# ESPMODULE-E_B_EL-VENOM.net
KiCad netlist of a schematic drawn in Altium Designer
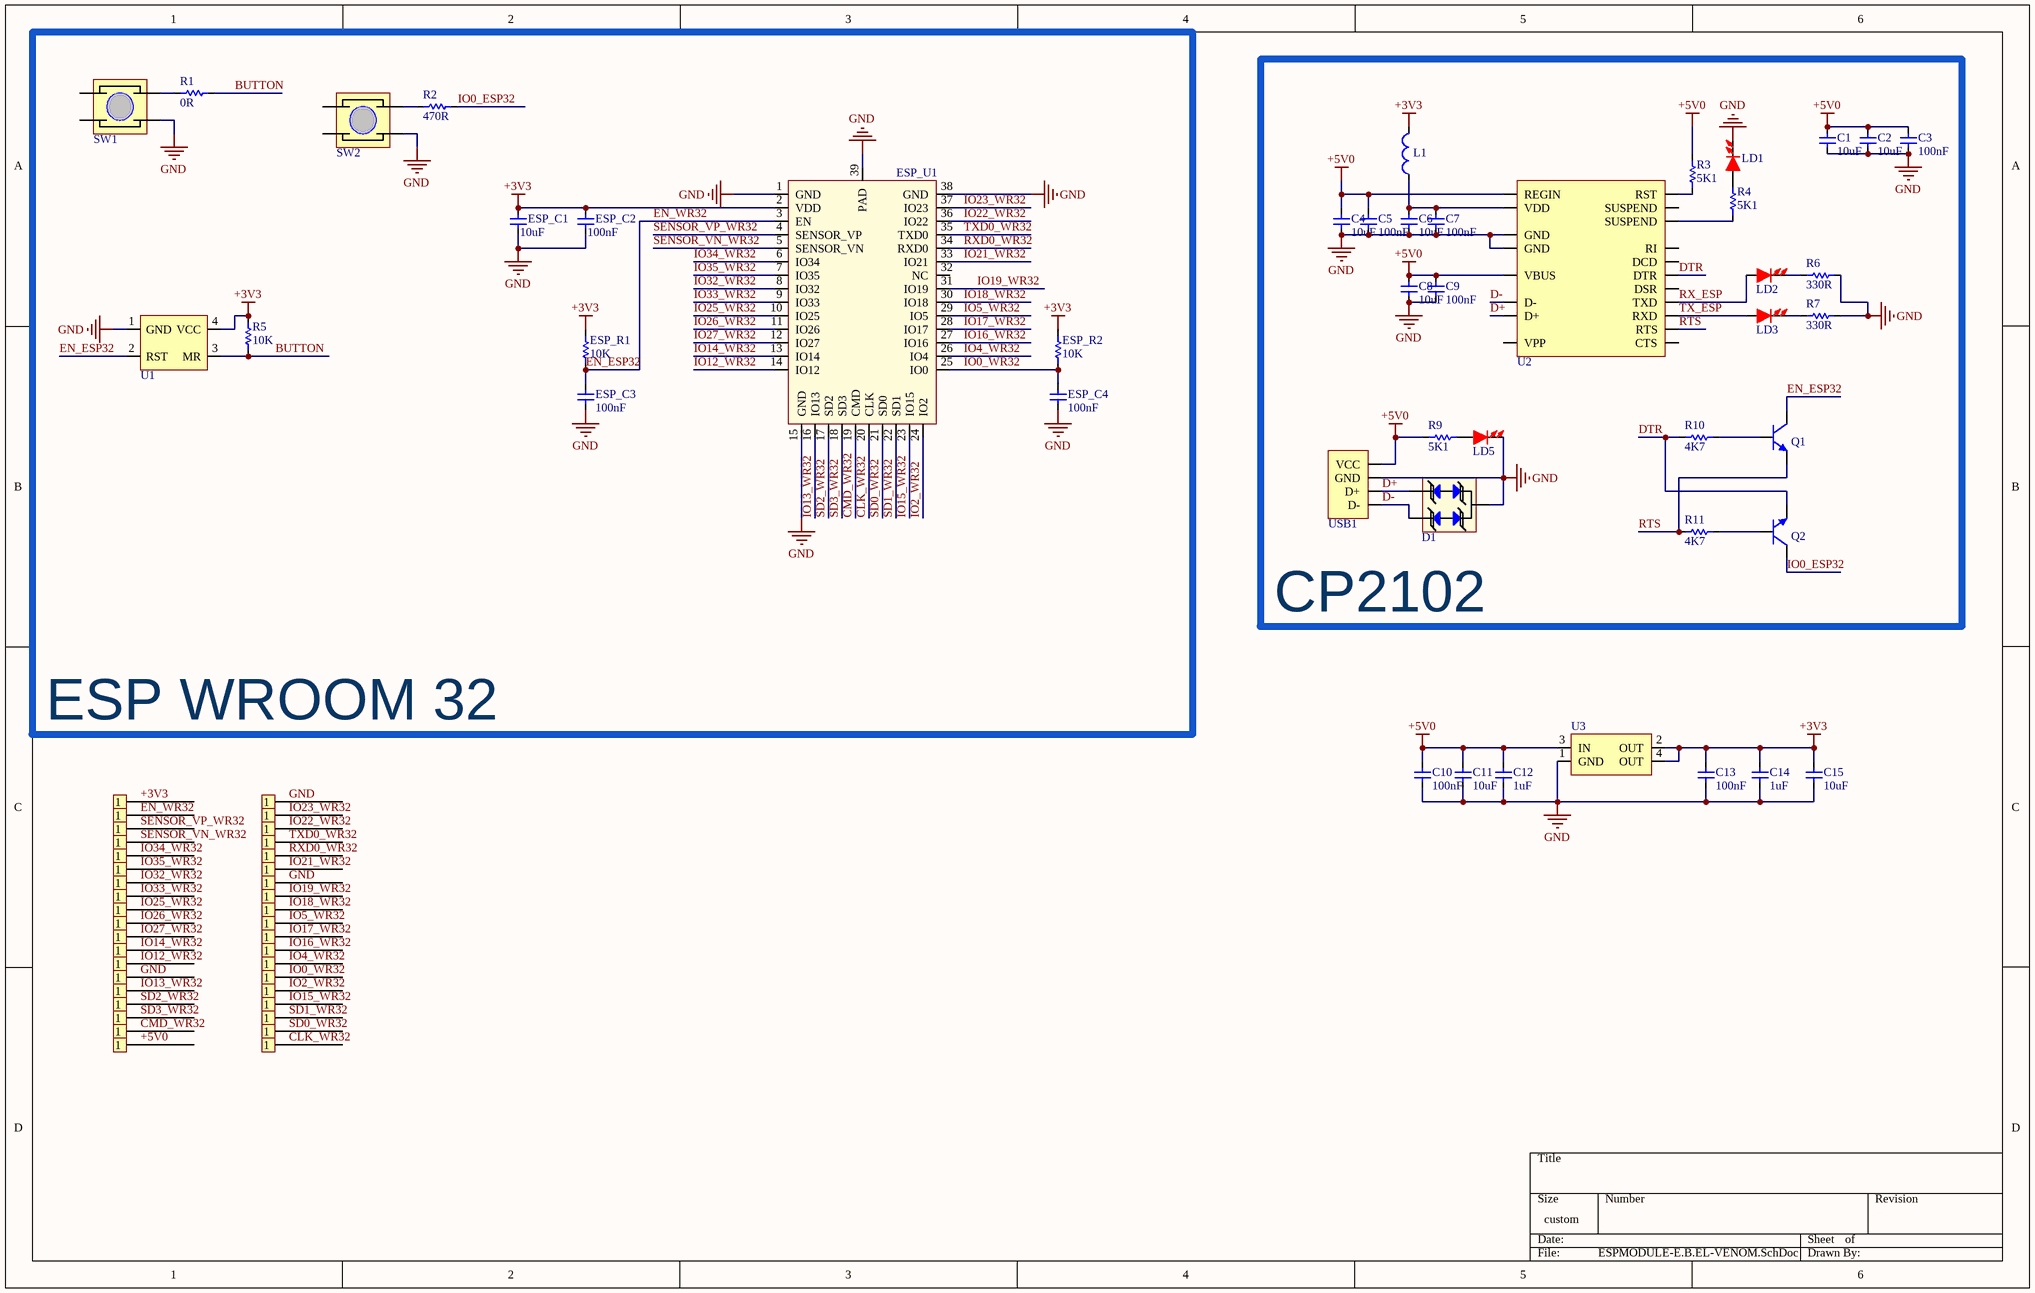
[diagram p0: ESPMODULE-E.B.EL-VENOM.SchDoc]

(export (version "E")
  (design (tool "Eeschema 10.0.6"))
  (components
    (comp (ref "C1")
      (value "10uF")
      (footprint "0805C")
      (description "CAP 0805 10uF 16V X5R")
      (libsource (lib "Ake Library") (part "Capacitor"))
    )
    (comp (ref "C2")
      (value "10uF")
      (footprint "0805C")
      (description "CAP 0805 10uF 16V X5R")
      (libsource (lib "Ake Library") (part "Capacitor"))
    )
    (comp (ref "C3")
      (value "100nF")
      (footprint "0603C")
      (description "CAP 0603 100nF 50V X7R")
      (libsource (lib "Ake Library") (part "Capacitor"))
    )
    (comp (ref "C4")
      (value "10uF")
      (footprint "0805C")
      (description "CAP 0805 10uF 16V X5R")
      (libsource (lib "Ake Library") (part "Capacitor"))
    )
    (comp (ref "C5")
      (value "100nF")
      (footprint "0603C")
      (description "CAP 0603 100nF 50V X7R")
      (libsource (lib "Ake Library") (part "Capacitor"))
    )
    (comp (ref "C6")
      (value "10uF")
      (footprint "0805C")
      (description "CAP 0805 10uF 16V X5R")
      (libsource (lib "Ake Library") (part "Capacitor"))
    )
    (comp (ref "C7")
      (value "100nF")
      (footprint "0603C")
      (description "CAP 0603 100nF 50V X7R")
      (libsource (lib "Ake Library") (part "Capacitor"))
    )
    (comp (ref "C8")
      (value "10uF")
      (footprint "0805C")
      (description "CAP 0805 10uF 16V X5R")
      (libsource (lib "Ake Library") (part "Capacitor"))
    )
    (comp (ref "C9")
      (value "100nF")
      (footprint "0603C")
      (description "CAP 0603 100nF 50V X7R")
      (libsource (lib "Ake Library") (part "Capacitor"))
    )
    (comp (ref "C10")
      (value "100nF")
      (footprint "0603C")
      (description "CAP 0603 100nF 50V X7R")
      (libsource (lib "Ake Library") (part "Capacitor"))
    )
    (comp (ref "C11")
      (value "10uF")
      (footprint "0805C")
      (description "CAP 0805 10uF 16V X5R")
      (libsource (lib "Ake Library") (part "Capacitor"))
    )
    (comp (ref "C12")
      (value "1uF")
      (footprint "0603C")
      (description "CAP 0603 1uF 16V X5R")
      (libsource (lib "Ake Library") (part "Capacitor"))
    )
    (comp (ref "C13")
      (value "100nF")
      (footprint "0603C")
      (description "CAP 0603 100nF 50V X7R")
      (libsource (lib "Ake Library") (part "Capacitor"))
    )
    (comp (ref "C14")
      (value "1uF")
      (footprint "0603C")
      (description "CAP 0603 1uF 16V X5R")
      (libsource (lib "Ake Library") (part "Capacitor"))
    )
    (comp (ref "C15")
      (value "10uF")
      (footprint "0805C")
      (description "CAP 0805 10uF 16V X5R")
      (libsource (lib "Ake Library") (part "Capacitor"))
    )
    (comp (ref "CON1")
      (value "Connector 1p")
      (footprint "HEADER 1 DIP ERKEK 180")
      (description "P.HEADER 1x40 PIN 180 DERECE DIP ERKEK")
      (libsource (lib "Ake Library") (part "Connector 1p"))
    )
    (comp (ref "CON2")
      (value "Connector 1p")
      (footprint "HEADER 1 DIP ERKEK 180")
      (description "P.HEADER 1x40 PIN 180 DERECE DIP ERKEK")
      (libsource (lib "Ake Library") (part "Connector 1p"))
    )
    (comp (ref "CON3")
      (value "Connector 1p")
      (footprint "HEADER 1 DIP ERKEK 180")
      (description "P.HEADER 1x40 PIN 180 DERECE DIP ERKEK")
      (libsource (lib "Ake Library") (part "Connector 1p"))
    )
    (comp (ref "CON4")
      (value "Connector 1p")
      (footprint "HEADER 1 DIP ERKEK 180")
      (description "P.HEADER 1x40 PIN 180 DERECE DIP ERKEK")
      (libsource (lib "Ake Library") (part "Connector 1p"))
    )
    (comp (ref "CON5")
      (value "Connector 1p")
      (footprint "HEADER 1 DIP ERKEK 180")
      (description "P.HEADER 1x40 PIN 180 DERECE DIP ERKEK")
      (libsource (lib "Ake Library") (part "Connector 1p"))
    )
    (comp (ref "CON6")
      (value "Connector 1p")
      (footprint "HEADER 1 DIP ERKEK 180")
      (description "P.HEADER 1x40 PIN 180 DERECE DIP ERKEK")
      (libsource (lib "Ake Library") (part "Connector 1p"))
    )
    (comp (ref "CON7")
      (value "Connector 1p")
      (footprint "HEADER 1 DIP ERKEK 180")
      (description "P.HEADER 1x40 PIN 180 DERECE DIP ERKEK")
      (libsource (lib "Ake Library") (part "Connector 1p"))
    )
    (comp (ref "CON8")
      (value "Connector 1p")
      (footprint "HEADER 1 DIP ERKEK 180")
      (description "P.HEADER 1x40 PIN 180 DERECE DIP ERKEK")
      (libsource (lib "Ake Library") (part "Connector 1p"))
    )
    (comp (ref "CON9")
      (value "Connector 1p")
      (footprint "HEADER 1 DIP ERKEK 180")
      (description "P.HEADER 1x40 PIN 180 DERECE DIP ERKEK")
      (libsource (lib "Ake Library") (part "Connector 1p"))
    )
    (comp (ref "CON10")
      (value "Connector 1p")
      (footprint "HEADER 1 DIP ERKEK 180")
      (description "P.HEADER 1x40 PIN 180 DERECE DIP ERKEK")
      (libsource (lib "Ake Library") (part "Connector 1p"))
    )
    (comp (ref "CON11")
      (value "Connector 1p")
      (footprint "HEADER 1 DIP ERKEK 180")
      (description "P.HEADER 1x40 PIN 180 DERECE DIP ERKEK")
      (libsource (lib "Ake Library") (part "Connector 1p"))
    )
    (comp (ref "CON12")
      (value "Connector 1p")
      (footprint "HEADER 1 DIP ERKEK 180")
      (description "P.HEADER 1x40 PIN 180 DERECE DIP ERKEK")
      (libsource (lib "Ake Library") (part "Connector 1p"))
    )
    (comp (ref "CON13")
      (value "Connector 1p")
      (footprint "HEADER 1 DIP ERKEK 180")
      (description "P.HEADER 1x40 PIN 180 DERECE DIP ERKEK")
      (libsource (lib "Ake Library") (part "Connector 1p"))
    )
    (comp (ref "CON14")
      (value "Connector 1p")
      (footprint "HEADER 1 DIP ERKEK 180")
      (description "P.HEADER 1x40 PIN 180 DERECE DIP ERKEK")
      (libsource (lib "Ake Library") (part "Connector 1p"))
    )
    (comp (ref "CON15")
      (value "Connector 1p")
      (footprint "HEADER 1 DIP ERKEK 180")
      (description "P.HEADER 1x40 PIN 180 DERECE DIP ERKEK")
      (libsource (lib "Ake Library") (part "Connector 1p"))
    )
    (comp (ref "CON16")
      (value "Connector 1p")
      (footprint "HEADER 1 DIP ERKEK 180")
      (description "P.HEADER 1x40 PIN 180 DERECE DIP ERKEK")
      (libsource (lib "Ake Library") (part "Connector 1p"))
    )
    (comp (ref "CON17")
      (value "Connector 1p")
      (footprint "HEADER 1 DIP ERKEK 180")
      (description "P.HEADER 1x40 PIN 180 DERECE DIP ERKEK")
      (libsource (lib "Ake Library") (part "Connector 1p"))
    )
    (comp (ref "CON18")
      (value "Connector 1p")
      (footprint "HEADER 1 DIP ERKEK 180")
      (description "P.HEADER 1x40 PIN 180 DERECE DIP ERKEK")
      (libsource (lib "Ake Library") (part "Connector 1p"))
    )
    (comp (ref "CON19")
      (value "Connector 1p")
      (footprint "HEADER 1 DIP ERKEK 180")
      (description "P.HEADER 1x40 PIN 180 DERECE DIP ERKEK")
      (libsource (lib "Ake Library") (part "Connector 1p"))
    )
    (comp (ref "CON20")
      (value "Connector 1p")
      (footprint "HEADER 1 DIP ERKEK 180")
      (description "P.HEADER 1x40 PIN 180 DERECE DIP ERKEK")
      (libsource (lib "Ake Library") (part "Connector 1p"))
    )
    (comp (ref "CON21")
      (value "Connector 1p")
      (footprint "HEADER 1 DIP ERKEK 180")
      (description "P.HEADER 1x40 PIN 180 DERECE DIP ERKEK")
      (libsource (lib "Ake Library") (part "Connector 1p"))
    )
    (comp (ref "CON22")
      (value "Connector 1p")
      (footprint "HEADER 1 DIP ERKEK 180")
      (description "P.HEADER 1x40 PIN 180 DERECE DIP ERKEK")
      (libsource (lib "Ake Library") (part "Connector 1p"))
    )
    (comp (ref "CON23")
      (value "Connector 1p")
      (footprint "HEADER 1 DIP ERKEK 180")
      (description "P.HEADER 1x40 PIN 180 DERECE DIP ERKEK")
      (libsource (lib "Ake Library") (part "Connector 1p"))
    )
    (comp (ref "CON24")
      (value "Connector 1p")
      (footprint "HEADER 1 DIP ERKEK 180")
      (description "P.HEADER 1x40 PIN 180 DERECE DIP ERKEK")
      (libsource (lib "Ake Library") (part "Connector 1p"))
    )
    (comp (ref "CON25")
      (value "Connector 1p")
      (footprint "HEADER 1 DIP ERKEK 180")
      (description "P.HEADER 1x40 PIN 180 DERECE DIP ERKEK")
      (libsource (lib "Ake Library") (part "Connector 1p"))
    )
    (comp (ref "CON26")
      (value "Connector 1p")
      (footprint "HEADER 1 DIP ERKEK 180")
      (description "P.HEADER 1x40 PIN 180 DERECE DIP ERKEK")
      (libsource (lib "Ake Library") (part "Connector 1p"))
    )
    (comp (ref "CON27")
      (value "Connector 1p")
      (footprint "HEADER 1 DIP ERKEK 180")
      (description "P.HEADER 1x40 PIN 180 DERECE DIP ERKEK")
      (libsource (lib "Ake Library") (part "Connector 1p"))
    )
    (comp (ref "CON28")
      (value "Connector 1p")
      (footprint "HEADER 1 DIP ERKEK 180")
      (description "P.HEADER 1x40 PIN 180 DERECE DIP ERKEK")
      (libsource (lib "Ake Library") (part "Connector 1p"))
    )
    (comp (ref "CON29")
      (value "Connector 1p")
      (footprint "HEADER 1 DIP ERKEK 180")
      (description "P.HEADER 1x40 PIN 180 DERECE DIP ERKEK")
      (libsource (lib "Ake Library") (part "Connector 1p"))
    )
    (comp (ref "CON30")
      (value "Connector 1p")
      (footprint "HEADER 1 DIP ERKEK 180")
      (description "P.HEADER 1x40 PIN 180 DERECE DIP ERKEK")
      (libsource (lib "Ake Library") (part "Connector 1p"))
    )
    (comp (ref "CON31")
      (value "Connector 1p")
      (footprint "HEADER 1 DIP ERKEK 180")
      (description "P.HEADER 1x40 PIN 180 DERECE DIP ERKEK")
      (libsource (lib "Ake Library") (part "Connector 1p"))
    )
    (comp (ref "CON32")
      (value "Connector 1p")
      (footprint "HEADER 1 DIP ERKEK 180")
      (description "P.HEADER 1x40 PIN 180 DERECE DIP ERKEK")
      (libsource (lib "Ake Library") (part "Connector 1p"))
    )
    (comp (ref "CON33")
      (value "Connector 1p")
      (footprint "HEADER 1 DIP ERKEK 180")
      (description "P.HEADER 1x40 PIN 180 DERECE DIP ERKEK")
      (libsource (lib "Ake Library") (part "Connector 1p"))
    )
    (comp (ref "CON34")
      (value "Connector 1p")
      (footprint "HEADER 1 DIP ERKEK 180")
      (description "P.HEADER 1x40 PIN 180 DERECE DIP ERKEK")
      (libsource (lib "Ake Library") (part "Connector 1p"))
    )
    (comp (ref "CON35")
      (value "Connector 1p")
      (footprint "HEADER 1 DIP ERKEK 180")
      (description "P.HEADER 1x40 PIN 180 DERECE DIP ERKEK")
      (libsource (lib "Ake Library") (part "Connector 1p"))
    )
    (comp (ref "CON36")
      (value "Connector 1p")
      (footprint "HEADER 1 DIP ERKEK 180")
      (description "P.HEADER 1x40 PIN 180 DERECE DIP ERKEK")
      (libsource (lib "Ake Library") (part "Connector 1p"))
    )
    (comp (ref "CON37")
      (value "Connector 1p")
      (footprint "HEADER 1 DIP ERKEK 180")
      (description "P.HEADER 1x40 PIN 180 DERECE DIP ERKEK")
      (libsource (lib "Ake Library") (part "Connector 1p"))
    )
    (comp (ref "CON38")
      (value "Connector 1p")
      (footprint "HEADER 1 DIP ERKEK 180")
      (description "P.HEADER 1x40 PIN 180 DERECE DIP ERKEK")
      (libsource (lib "Ake Library") (part "Connector 1p"))
    )
    (comp (ref "D1")
      (value "TVS Diode 3p")
      (footprint "SOT23")
      (description "CDSOT23-SM712 DIODE TVS 400W 26V")
      (libsource (lib "Ake Library") (part "TVS Diode 3p"))
    )
    (comp (ref "ESP_C1")
      (value "10uF")
      (footprint "0805C")
      (description "CAP 0805 10uF 16V X5R")
      (libsource (lib "Ake Library") (part "Capacitor"))
    )
    (comp (ref "ESP_C2")
      (value "100nF")
      (footprint "0603C")
      (description "CAP 0603 100nF 50V X7R")
      (libsource (lib "Ake Library") (part "Capacitor"))
    )
    (comp (ref "ESP_C3")
      (value "100nF")
      (footprint "0603C")
      (description "CAP 0603 100nF 50V X7R")
      (libsource (lib "Ake Library") (part "Capacitor"))
    )
    (comp (ref "ESP_C4")
      (value "100nF")
      (footprint "0603C")
      (description "CAP 0603 100nF 50V X7R")
      (libsource (lib "Ake Library") (part "Capacitor"))
    )
    (comp (ref "ESP_R1")
      (value "10K")
      (footprint "0603R")
      (description "RES 0603 10K 1% 1/10W-S")
      (libsource (lib "Ake Library") (part "Resistor"))
    )
    (comp (ref "ESP_R2")
      (value "10K")
      (footprint "0603R")
      (description "RES 0603 10K 1% 1/10W-S")
      (libsource (lib "Ake Library") (part "Resistor"))
    )
    (comp (ref "ESP_U1")
      (value "ESP_WROOM_32")
      (footprint "ESP-WROOM-32")
      (description "ESP-WROOM-32 WİFİ MODULÜ")
      (libsource (lib "Ake Library") (part "ESP-WROOM-32"))
    )
    (comp (ref "L1")
      (value "Ferrite")
      (footprint "0805L")
      (description "INDUCTOR 2K5 SMD 0805 FERRITE 250mA")
      (libsource (lib "Ake Library") (part "Ferrite"))
    )
    (comp (ref "LD1")
      (value "LED")
      (footprint "0805LED")
      (description "LED GREEN SMD 0805")
      (libsource (lib "Ake Library") (part "LED"))
    )
    (comp (ref "LD2")
      (value "LED")
      (footprint "0805LED")
      (description "LED GREEN SMD 0805")
      (libsource (lib "Ake Library") (part "LED"))
    )
    (comp (ref "LD3")
      (value "LED")
      (footprint "0805LED")
      (description "LED BLUE SMD 0805")
      (libsource (lib "Ake Library") (part "LED"))
    )
    (comp (ref "LD5")
      (value "LED")
      (footprint "0805LED")
      (description "LED RED SMD 0805")
      (libsource (lib "Ake Library") (part "LED"))
    )
    (comp (ref "Q1")
      (value "NPN")
      (footprint "SOT23")
      (description "TRANSISTOR NPN BC817 0.5A SOT23")
      (libsource (lib "Ake Library") (part "NPN"))
    )
    (comp (ref "Q2")
      (value "NPN")
      (footprint "SOT23")
      (description "TRANSISTOR NPN BC817 0.5A SOT23")
      (libsource (lib "Ake Library") (part "NPN"))
    )
    (comp (ref "R1")
      (value "0R")
      (footprint "0603R")
      (description "RES 0603 0R 5% 1/10W-S")
      (libsource (lib "Ake Library") (part "Resistor"))
    )
    (comp (ref "R2")
      (value "470R")
      (footprint "0603R")
      (description "RES 0603 470R 1% 1/10W-S")
      (libsource (lib "Ake Library") (part "Resistor"))
    )
    (comp (ref "R3")
      (value "5K1")
      (footprint "0603R")
      (description "RES 0603 5K1 5% 1/10W-S")
      (libsource (lib "Ake Library") (part "Resistor"))
    )
    (comp (ref "R4")
      (value "5K1")
      (footprint "0603R")
      (description "RES 0603 5K1 5% 1/10W-S")
      (libsource (lib "Ake Library") (part "Resistor"))
    )
    (comp (ref "R5")
      (value "10K")
      (footprint "0603R")
      (description "RES 0603 10K 1% 1/10W-S")
      (libsource (lib "Ake Library") (part "Resistor"))
    )
    (comp (ref "R6")
      (value "330R")
      (footprint "0603R")
      (description "RES 0603 330R 5% 1/10W-S")
      (libsource (lib "Ake Library") (part "Resistor"))
    )
    (comp (ref "R7")
      (value "330R")
      (footprint "0603R")
      (description "RES 0603 330R 5% 1/10W-S")
      (libsource (lib "Ake Library") (part "Resistor"))
    )
    (comp (ref "R9")
      (value "5K1")
      (footprint "0603R")
      (description "RES 0603 5K1 5% 1/10W-S")
      (libsource (lib "Ake Library") (part "Resistor"))
    )
    (comp (ref "R10")
      (value "4K7")
      (footprint "0603R")
      (description "RES 0603 4K7 5% 1/10W-S")
      (libsource (lib "Ake Library") (part "Resistor"))
    )
    (comp (ref "R11")
      (value "4K7")
      (footprint "0603R")
      (description "RES 0603 4K7 5% 1/10W-S")
      (libsource (lib "Ake Library") (part "Resistor"))
    )
    (comp (ref "SW1")
      (value "Button")
      (footprint "BUTTON 6x6 4.3MM")
      (description "BUTTON 6x6 4.3MM")
      (libsource (lib "Ake Library") (part "Button"))
    )
    (comp (ref "SW2")
      (value "Button")
      (footprint "BUTTON 6x6 4.3MM")
      (description "BUTTON 6x6 4.3MM")
      (libsource (lib "Ake Library") (part "Button"))
    )
    (comp (ref "U1") (value "CAT811") (footprint "SOT-143") (libsource (lib "AkeLib") (part "CAT811")))
    (comp (ref "U2")
      (value "CP2102")
      (footprint "QFN-28 5x5x0.5")
      (description "CP2102-GMR USB TO UART BRIDGE 28VQFN")
      (libsource (lib "Ake Library") (part "CP2102"))
    )
    (comp (ref "U3")
      (value "LM1117")
      (footprint "SOT223")
      (description "REG 1117 3V3 SOT223")
      (libsource (lib "Ake Library") (part "LM1117"))
    )
    (comp (ref "USB1")
      (value "USB")
      (footprint "USB B MICRO 90")
      (description "MICRO USB CONNECTOR TYPE B 90")
      (libsource (lib "Ake Library") (part "USB"))
    )
  )
  (nets
    (net (code "1") (name "+3V3") (class "Default")
      (node (ref "C13") (pin "2") (pinfunction "2_2") (pintype "passive"))
      (node (ref "C14") (pin "2") (pinfunction "2_2") (pintype "passive"))
      (node (ref "C15") (pin "2") (pinfunction "2_2") (pintype "passive"))
      (node (ref "CON1") (pin "1") (pinfunction "1_1") (pintype "passive"))
      (node (ref "ESP_C1") (pin "2") (pinfunction "2_2") (pintype "passive"))
      (node (ref "ESP_C2") (pin "2") (pinfunction "2_2") (pintype "passive"))
      (node (ref "ESP_R1") (pin "2") (pinfunction "2_2") (pintype "passive"))
      (node (ref "ESP_R2") (pin "2") (pinfunction "2_2") (pintype "passive"))
      (node (ref "ESP_U1") (pin "2") (pinfunction "VDD_2") (pintype "passive"))
      (node (ref "L1") (pin "2") (pinfunction "2_2") (pintype "passive"))
      (node (ref "R5") (pin "2") (pinfunction "2_2") (pintype "passive"))
      (node (ref "U1") (pin "4") (pinfunction "VCC_4") (pintype "passive"))
      (node (ref "U3") (pin "2") (pinfunction "OUT_2") (pintype "power_in"))
      (node (ref "U3") (pin "4") (pinfunction "OUT_4") (pintype "power_in"))
    )
    (net (code "2") (name "+5V0") (class "Default")
      (node (ref "C1") (pin "2") (pinfunction "2_2") (pintype "passive"))
      (node (ref "C10") (pin "2") (pinfunction "2_2") (pintype "passive"))
      (node (ref "C11") (pin "2") (pinfunction "2_2") (pintype "passive"))
      (node (ref "C12") (pin "2") (pinfunction "2_2") (pintype "passive"))
      (node (ref "C2") (pin "2") (pinfunction "2_2") (pintype "passive"))
      (node (ref "C3") (pin "2") (pinfunction "2_2") (pintype "passive"))
      (node (ref "C4") (pin "2") (pinfunction "2_2") (pintype "passive"))
      (node (ref "C5") (pin "2") (pinfunction "2_2") (pintype "passive"))
      (node (ref "C8") (pin "2") (pinfunction "2_2") (pintype "passive"))
      (node (ref "C9") (pin "2") (pinfunction "2_2") (pintype "passive"))
      (node (ref "CON37") (pin "1") (pinfunction "1_1") (pintype "passive"))
      (node (ref "R3") (pin "2") (pinfunction "2_2") (pintype "passive"))
      (node (ref "R9") (pin "1") (pinfunction "1_1") (pintype "passive"))
      (node (ref "U2") (pin "7") (pinfunction "REGIN_7") (pintype "passive"))
      (node (ref "U2") (pin "8") (pinfunction "VBUS_8") (pintype "passive"))
      (node (ref "U3") (pin "3") (pinfunction "IN_3") (pintype "power_in"))
      (node (ref "USB1") (pin "VCC") (pinfunction "VCC_VCC") (pintype "passive"))
    )
    (net (code "3") (name "/BUTTON") (class "Default")
      (node (ref "R1") (pin "2") (pinfunction "2_2") (pintype "passive"))
      (node (ref "R5") (pin "1") (pinfunction "1_1") (pintype "passive"))
      (node (ref "U1") (pin "3") (pinfunction "MR_3") (pintype "passive"))
    )
    (net (code "4") (name "/CLK_WR32") (class "Default")
      (node (ref "CON38") (pin "1") (pinfunction "1_1") (pintype "passive"))
      (node (ref "ESP_U1") (pin "20") (pinfunction "CLK_20") (pintype "passive"))
    )
    (net (code "5") (name "/CMD_WR32") (class "Default")
      (node (ref "CON35") (pin "1") (pinfunction "1_1") (pintype "passive"))
      (node (ref "ESP_U1") (pin "19") (pinfunction "CMD_19") (pintype "passive"))
    )
    (net (code "6") (name "/D+") (class "Default")
      (node (ref "D1") (pin "2") (pinfunction "2_2") (pintype "passive"))
      (node (ref "U2") (pin "4") (pinfunction "D+_4") (pintype "passive"))
      (node (ref "USB1") (pin "D+") (pinfunction "D+_D+") (pintype "passive"))
    )
    (net (code "7") (name "/D-") (class "Default")
      (node (ref "D1") (pin "1") (pinfunction "1_1") (pintype "passive"))
      (node (ref "U2") (pin "5") (pinfunction "D-_5") (pintype "passive"))
      (node (ref "USB1") (pin "D-") (pinfunction "D-_D-") (pintype "passive"))
    )
    (net (code "8") (name "/DTR") (class "Default")
      (node (ref "Q2") (pin "2") (pinfunction "E_2") (pintype "passive"))
      (node (ref "R10") (pin "1") (pinfunction "1_1") (pintype "passive"))
      (node (ref "U2") (pin "28") (pinfunction "DTR_28") (pintype "passive"))
    )
    (net (code "9") (name "/EN_ESP32") (class "Default")
      (node (ref "CON3") (pin "1") (pinfunction "1_1") (pintype "passive"))
      (node (ref "ESP_C3") (pin "2") (pinfunction "2_2") (pintype "passive"))
      (node (ref "ESP_R1") (pin "1") (pinfunction "1_1") (pintype "passive"))
      (node (ref "ESP_U1") (pin "3") (pinfunction "EN_3") (pintype "passive"))
      (node (ref "Q1") (pin "3") (pinfunction "C_3") (pintype "passive"))
      (node (ref "U1") (pin "2") (pinfunction "RST_2") (pintype "passive"))
    )
    (net (code "10") (name "/IO0_ESP32") (class "Default")
      (node (ref "Q2") (pin "3") (pinfunction "C_3") (pintype "passive"))
      (node (ref "R2") (pin "2") (pinfunction "2_2") (pintype "passive"))
    )
    (net (code "11") (name "/IO0_WR32") (class "Default")
      (node (ref "CON28") (pin "1") (pinfunction "1_1") (pintype "passive"))
      (node (ref "ESP_C4") (pin "2") (pinfunction "2_2") (pintype "passive"))
      (node (ref "ESP_R2") (pin "1") (pinfunction "1_1") (pintype "passive"))
      (node (ref "ESP_U1") (pin "25") (pinfunction "IO0_25") (pintype "passive"))
    )
    (net (code "12") (name "/IO2_WR32") (class "Default")
      (node (ref "CON30") (pin "1") (pinfunction "1_1") (pintype "passive"))
      (node (ref "ESP_U1") (pin "24") (pinfunction "IO2_24") (pintype "passive"))
    )
    (net (code "13") (name "/IO4_WR32") (class "Default")
      (node (ref "CON26") (pin "1") (pinfunction "1_1") (pintype "passive"))
      (node (ref "ESP_U1") (pin "26") (pinfunction "IO4_26") (pintype "passive"))
    )
    (net (code "14") (name "/IO5_WR32") (class "Default")
      (node (ref "CON20") (pin "1") (pinfunction "1_1") (pintype "passive"))
      (node (ref "ESP_U1") (pin "29") (pinfunction "IO5_29") (pintype "passive"))
    )
    (net (code "15") (name "/IO12_WR32") (class "Default")
      (node (ref "CON25") (pin "1") (pinfunction "1_1") (pintype "passive"))
      (node (ref "ESP_U1") (pin "14") (pinfunction "IO12_14") (pintype "passive"))
    )
    (net (code "16") (name "/IO13_WR32") (class "Default")
      (node (ref "CON29") (pin "1") (pinfunction "1_1") (pintype "passive"))
      (node (ref "ESP_U1") (pin "16") (pinfunction "IO13_16") (pintype "passive"))
    )
    (net (code "17") (name "/IO14_WR32") (class "Default")
      (node (ref "CON23") (pin "1") (pinfunction "1_1") (pintype "passive"))
      (node (ref "ESP_U1") (pin "13") (pinfunction "IO14_13") (pintype "passive"))
    )
    (net (code "18") (name "/IO15_WR32") (class "Default")
      (node (ref "CON32") (pin "1") (pinfunction "1_1") (pintype "passive"))
      (node (ref "ESP_U1") (pin "23") (pinfunction "IO15_23") (pintype "passive"))
    )
    (net (code "19") (name "/IO16_WR32") (class "Default")
      (node (ref "CON24") (pin "1") (pinfunction "1_1") (pintype "passive"))
      (node (ref "ESP_U1") (pin "27") (pinfunction "IO16_27") (pintype "passive"))
    )
    (net (code "20") (name "/IO17_WR32") (class "Default")
      (node (ref "CON22") (pin "1") (pinfunction "1_1") (pintype "passive"))
      (node (ref "ESP_U1") (pin "28") (pinfunction "IO17_28") (pintype "passive"))
    )
    (net (code "21") (name "/IO18_WR32") (class "Default")
      (node (ref "CON18") (pin "1") (pinfunction "1_1") (pintype "passive"))
      (node (ref "ESP_U1") (pin "30") (pinfunction "IO18_30") (pintype "passive"))
    )
    (net (code "22") (name "/IO19_WR32") (class "Default")
      (node (ref "CON16") (pin "1") (pinfunction "1_1") (pintype "passive"))
      (node (ref "ESP_U1") (pin "31") (pinfunction "IO19_31") (pintype "passive"))
    )
    (net (code "23") (name "/IO21_WR32") (class "Default")
      (node (ref "CON12") (pin "1") (pinfunction "1_1") (pintype "passive"))
      (node (ref "ESP_U1") (pin "33") (pinfunction "IO21_33") (pintype "passive"))
    )
    (net (code "24") (name "/IO22_WR32") (class "Default")
      (node (ref "CON6") (pin "1") (pinfunction "1_1") (pintype "passive"))
      (node (ref "ESP_U1") (pin "36") (pinfunction "IO22_36") (pintype "passive"))
    )
    (net (code "25") (name "/IO23_WR32") (class "Default")
      (node (ref "CON4") (pin "1") (pinfunction "1_1") (pintype "passive"))
      (node (ref "ESP_U1") (pin "37") (pinfunction "IO23_37") (pintype "passive"))
    )
    (net (code "26") (name "/IO25_WR32") (class "Default")
      (node (ref "CON17") (pin "1") (pinfunction "1_1") (pintype "passive"))
      (node (ref "ESP_U1") (pin "10") (pinfunction "IO25_10") (pintype "passive"))
    )
    (net (code "27") (name "/IO26_WR32") (class "Default")
      (node (ref "CON19") (pin "1") (pinfunction "1_1") (pintype "passive"))
      (node (ref "ESP_U1") (pin "11") (pinfunction "IO26_11") (pintype "passive"))
    )
    (net (code "28") (name "/IO27_WR32") (class "Default")
      (node (ref "CON21") (pin "1") (pinfunction "1_1") (pintype "passive"))
      (node (ref "ESP_U1") (pin "12") (pinfunction "IO27_12") (pintype "passive"))
    )
    (net (code "29") (name "/IO32_WR32") (class "Default")
      (node (ref "CON13") (pin "1") (pinfunction "1_1") (pintype "passive"))
      (node (ref "ESP_U1") (pin "8") (pinfunction "IO32_8") (pintype "passive"))
    )
    (net (code "30") (name "/IO33_WR32") (class "Default")
      (node (ref "CON15") (pin "1") (pinfunction "1_1") (pintype "passive"))
      (node (ref "ESP_U1") (pin "9") (pinfunction "IO33_9") (pintype "passive"))
    )
    (net (code "31") (name "/IO34_WR32") (class "Default")
      (node (ref "CON9") (pin "1") (pinfunction "1_1") (pintype "passive"))
      (node (ref "ESP_U1") (pin "6") (pinfunction "IO34_6") (pintype "passive"))
    )
    (net (code "32") (name "/IO35_WR32") (class "Default")
      (node (ref "CON11") (pin "1") (pinfunction "1_1") (pintype "passive"))
      (node (ref "ESP_U1") (pin "7") (pinfunction "IO35_7") (pintype "passive"))
    )
    (net (code "33") (name "/RTS") (class "Default")
      (node (ref "Q1") (pin "2") (pinfunction "E_2") (pintype "passive"))
      (node (ref "R11") (pin "1") (pinfunction "1_1") (pintype "passive"))
      (node (ref "U2") (pin "24") (pinfunction "RTS_24") (pintype "passive"))
    )
    (net (code "34") (name "/RXD0_WR32") (class "Default")
      (node (ref "CON10") (pin "1") (pinfunction "1_1") (pintype "passive"))
      (node (ref "ESP_U1") (pin "34") (pinfunction "RXD0_34") (pintype "passive"))
    )
    (net (code "35") (name "/RX_ESP") (class "Default")
      (node (ref "LD2") (pin "1") (pinfunction "A_1") (pintype "passive"))
      (node (ref "U2") (pin "26") (pinfunction "TXD_26") (pintype "passive"))
    )
    (net (code "36") (name "/SD0_WR32") (class "Default")
      (node (ref "CON36") (pin "1") (pinfunction "1_1") (pintype "passive"))
      (node (ref "ESP_U1") (pin "21") (pinfunction "SD0_21") (pintype "passive"))
    )
    (net (code "37") (name "/SD1_WR32") (class "Default")
      (node (ref "CON34") (pin "1") (pinfunction "1_1") (pintype "passive"))
      (node (ref "ESP_U1") (pin "22") (pinfunction "SD1_22") (pintype "passive"))
    )
    (net (code "38") (name "/SD2_WR32") (class "Default")
      (node (ref "CON31") (pin "1") (pinfunction "1_1") (pintype "passive"))
      (node (ref "ESP_U1") (pin "17") (pinfunction "SD2_17") (pintype "passive"))
    )
    (net (code "39") (name "/SD3_WR32") (class "Default")
      (node (ref "CON33") (pin "1") (pinfunction "1_1") (pintype "passive"))
      (node (ref "ESP_U1") (pin "18") (pinfunction "SD3_18") (pintype "passive"))
    )
    (net (code "40") (name "/SENSOR_VN_WR32") (class "Default")
      (node (ref "CON7") (pin "1") (pinfunction "1_1") (pintype "passive"))
      (node (ref "ESP_U1") (pin "5") (pinfunction "SENSOR_VN_5") (pintype "passive"))
    )
    (net (code "41") (name "/SENSOR_VP_WR32") (class "Default")
      (node (ref "CON5") (pin "1") (pinfunction "1_1") (pintype "passive"))
      (node (ref "ESP_U1") (pin "4") (pinfunction "SENSOR_VP_4") (pintype "passive"))
    )
    (net (code "42") (name "/TXD0_WR32") (class "Default")
      (node (ref "CON8") (pin "1") (pinfunction "1_1") (pintype "passive"))
      (node (ref "ESP_U1") (pin "35") (pinfunction "TXD0_35") (pintype "passive"))
    )
    (net (code "43") (name "/TX_ESP") (class "Default")
      (node (ref "LD3") (pin "1") (pinfunction "A_1") (pintype "passive"))
      (node (ref "U2") (pin "25") (pinfunction "RXD_25") (pintype "passive"))
    )
    (net (code "44") (name "GND") (class "Default")
      (node (ref "C1") (pin "1") (pinfunction "1_1") (pintype "passive"))
      (node (ref "C10") (pin "1") (pinfunction "1_1") (pintype "passive"))
      (node (ref "C11") (pin "1") (pinfunction "1_1") (pintype "passive"))
      (node (ref "C12") (pin "1") (pinfunction "1_1") (pintype "passive"))
      (node (ref "C13") (pin "1") (pinfunction "1_1") (pintype "passive"))
      (node (ref "C14") (pin "1") (pinfunction "1_1") (pintype "passive"))
      (node (ref "C15") (pin "1") (pinfunction "1_1") (pintype "passive"))
      (node (ref "C2") (pin "1") (pinfunction "1_1") (pintype "passive"))
      (node (ref "C3") (pin "1") (pinfunction "1_1") (pintype "passive"))
      (node (ref "C4") (pin "1") (pinfunction "1_1") (pintype "passive"))
      (node (ref "C5") (pin "1") (pinfunction "1_1") (pintype "passive"))
      (node (ref "C6") (pin "1") (pinfunction "1_1") (pintype "passive"))
      (node (ref "C7") (pin "1") (pinfunction "1_1") (pintype "passive"))
      (node (ref "C8") (pin "1") (pinfunction "1_1") (pintype "passive"))
      (node (ref "C9") (pin "1") (pinfunction "1_1") (pintype "passive"))
      (node (ref "CON14") (pin "1") (pinfunction "1_1") (pintype "passive"))
      (node (ref "CON2") (pin "1") (pinfunction "1_1") (pintype "passive"))
      (node (ref "CON27") (pin "1") (pinfunction "1_1") (pintype "passive"))
      (node (ref "D1") (pin "3") (pinfunction "3_3") (pintype "passive"))
      (node (ref "ESP_C1") (pin "1") (pinfunction "1_1") (pintype "passive"))
      (node (ref "ESP_C2") (pin "1") (pinfunction "1_1") (pintype "passive"))
      (node (ref "ESP_C3") (pin "1") (pinfunction "1_1") (pintype "passive"))
      (node (ref "ESP_C4") (pin "1") (pinfunction "1_1") (pintype "passive"))
      (node (ref "ESP_U1") (pin "1") (pinfunction "GND_1") (pintype "passive"))
      (node (ref "ESP_U1") (pin "15") (pinfunction "GND_15") (pintype "passive"))
      (node (ref "ESP_U1") (pin "38") (pinfunction "GND_38") (pintype "passive"))
      (node (ref "ESP_U1") (pin "39") (pinfunction "PAD_39") (pintype "passive"))
      (node (ref "LD1") (pin "2") (pinfunction "K_2") (pintype "passive"))
      (node (ref "LD5") (pin "2") (pinfunction "K_2") (pintype "passive"))
      (node (ref "R6") (pin "2") (pinfunction "2_2") (pintype "passive"))
      (node (ref "R7") (pin "2") (pinfunction "2_2") (pintype "passive"))
      (node (ref "SW1") (pin "3") (pinfunction "3_3") (pintype "passive"))
      (node (ref "SW2") (pin "3") (pinfunction "3_3") (pintype "passive"))
      (node (ref "U1") (pin "1") (pinfunction "GND_1") (pintype "passive"))
      (node (ref "U2") (pin "29") (pinfunction "GND_29") (pintype "passive"))
      (node (ref "U2") (pin "3") (pinfunction "GND_3") (pintype "passive"))
      (node (ref "U3") (pin "1") (pinfunction "GND_1") (pintype "power_in"))
      (node (ref "USB1") (pin "GND") (pinfunction "GND_GND") (pintype "passive"))
    )
    (net (code "45") (name "Net-(LD1-A)") (class "Default")
      (node (ref "LD1") (pin "1") (pinfunction "A_1") (pintype "passive"))
      (node (ref "R4") (pin "1") (pinfunction "1_1") (pintype "passive"))
    )
    (net (code "46") (name "Net-(LD2-K)") (class "Default")
      (node (ref "LD2") (pin "2") (pinfunction "K_2") (pintype "passive"))
      (node (ref "R6") (pin "1") (pinfunction "1_1") (pintype "passive"))
    )
    (net (code "47") (name "Net-(LD3-K)") (class "Default")
      (node (ref "LD3") (pin "2") (pinfunction "K_2") (pintype "passive"))
      (node (ref "R7") (pin "1") (pinfunction "1_1") (pintype "passive"))
    )
    (net (code "48") (name "Net-(LD5-A)") (class "Default")
      (node (ref "LD5") (pin "1") (pinfunction "A_1") (pintype "passive"))
      (node (ref "R9") (pin "2") (pinfunction "2_2") (pintype "passive"))
    )
    (net (code "49") (name "Net-(Q1-B)") (class "Default")
      (node (ref "Q1") (pin "1") (pinfunction "B_1") (pintype "passive"))
      (node (ref "R10") (pin "2") (pinfunction "2_2") (pintype "passive"))
    )
    (net (code "50") (name "Net-(Q2-B)") (class "Default")
      (node (ref "Q2") (pin "1") (pinfunction "B_1") (pintype "passive"))
      (node (ref "R11") (pin "2") (pinfunction "2_2") (pintype "passive"))
    )
    (net (code "51") (name "Net-(R1-Pad1)") (class "Default")
      (node (ref "R1") (pin "1") (pinfunction "1_1") (pintype "passive"))
      (node (ref "SW1") (pin "4") (pinfunction "4_4") (pintype "passive"))
    )
    (net (code "52") (name "Net-(R2-Pad1)") (class "Default")
      (node (ref "R2") (pin "1") (pinfunction "1_1") (pintype "passive"))
      (node (ref "SW2") (pin "4") (pinfunction "4_4") (pintype "passive"))
    )
    (net (code "53") (name "Net-(R4-Pad2)") (class "Default")
      (node (ref "R4") (pin "2") (pinfunction "2_2") (pintype "passive"))
      (node (ref "U2") (pin "11") (pinfunction "SUSPEND_11") (pintype "passive"))
    )
    (net (code "54") (name "Net-(U2-RST)") (class "Default")
      (node (ref "R3") (pin "1") (pinfunction "1_1") (pintype "passive"))
      (node (ref "U2") (pin "9") (pinfunction "RST_9") (pintype "passive"))
    )
    (net (code "55") (name "Net-(U2-VDD)") (class "Default")
      (node (ref "C6") (pin "2") (pinfunction "2_2") (pintype "passive"))
      (node (ref "C7") (pin "2") (pinfunction "2_2") (pintype "passive"))
      (node (ref "L1") (pin "1") (pinfunction "1_1") (pintype "passive"))
      (node (ref "U2") (pin "6") (pinfunction "VDD_6") (pintype "passive"))
    )
    (net (code "56") (name "unconnected-(ESP_U1-NC-Pad32)") (class "Default")
      (node (ref "ESP_U1") (pin "32") (pinfunction "NC_32") (pintype "passive"))
    )
    (net (code "57") (name "unconnected-(SW1-Pad1)") (class "Default")
      (node (ref "SW1") (pin "1") (pinfunction "1_1") (pintype "passive"))
    )
    (net (code "58") (name "unconnected-(SW1-Pad2)") (class "Default")
      (node (ref "SW1") (pin "2") (pinfunction "2_2") (pintype "passive"))
    )
    (net (code "59") (name "unconnected-(SW2-Pad1)") (class "Default")
      (node (ref "SW2") (pin "1") (pinfunction "1_1") (pintype "passive"))
    )
    (net (code "60") (name "unconnected-(SW2-Pad2)") (class "Default")
      (node (ref "SW2") (pin "2") (pinfunction "2_2") (pintype "passive"))
    )
    (net (code "61") (name "unconnected-(U2-CTS-Pad23)") (class "Default")
      (node (ref "U2") (pin "23") (pinfunction "CTS_23") (pintype "passive"))
    )
    (net (code "62") (name "unconnected-(U2-DCD-Pad1)") (class "Default")
      (node (ref "U2") (pin "1") (pinfunction "DCD_1") (pintype "passive"))
    )
    (net (code "63") (name "unconnected-(U2-DSR-Pad27)") (class "Default")
      (node (ref "U2") (pin "27") (pinfunction "DSR_27") (pintype "passive"))
    )
    (net (code "64") (name "unconnected-(U2-RI-Pad2)") (class "Default")
      (node (ref "U2") (pin "2") (pinfunction "RI_2") (pintype "passive"))
    )
    (net (code "65") (name "unconnected-(U2-SUSPEND-Pad12)") (class "Default")
      (node (ref "U2") (pin "12") (pinfunction "SUSPEND_12") (pintype "passive"))
    )
    (net (code "66") (name "unconnected-(U2-VPP-Pad18)") (class "Default")
      (node (ref "U2") (pin "18") (pinfunction "VPP_18") (pintype "passive"))
    )
  )
)
